# 16_-ETH_SWITCH.net
KiCad netlist of a schematic drawn in Altium Designer
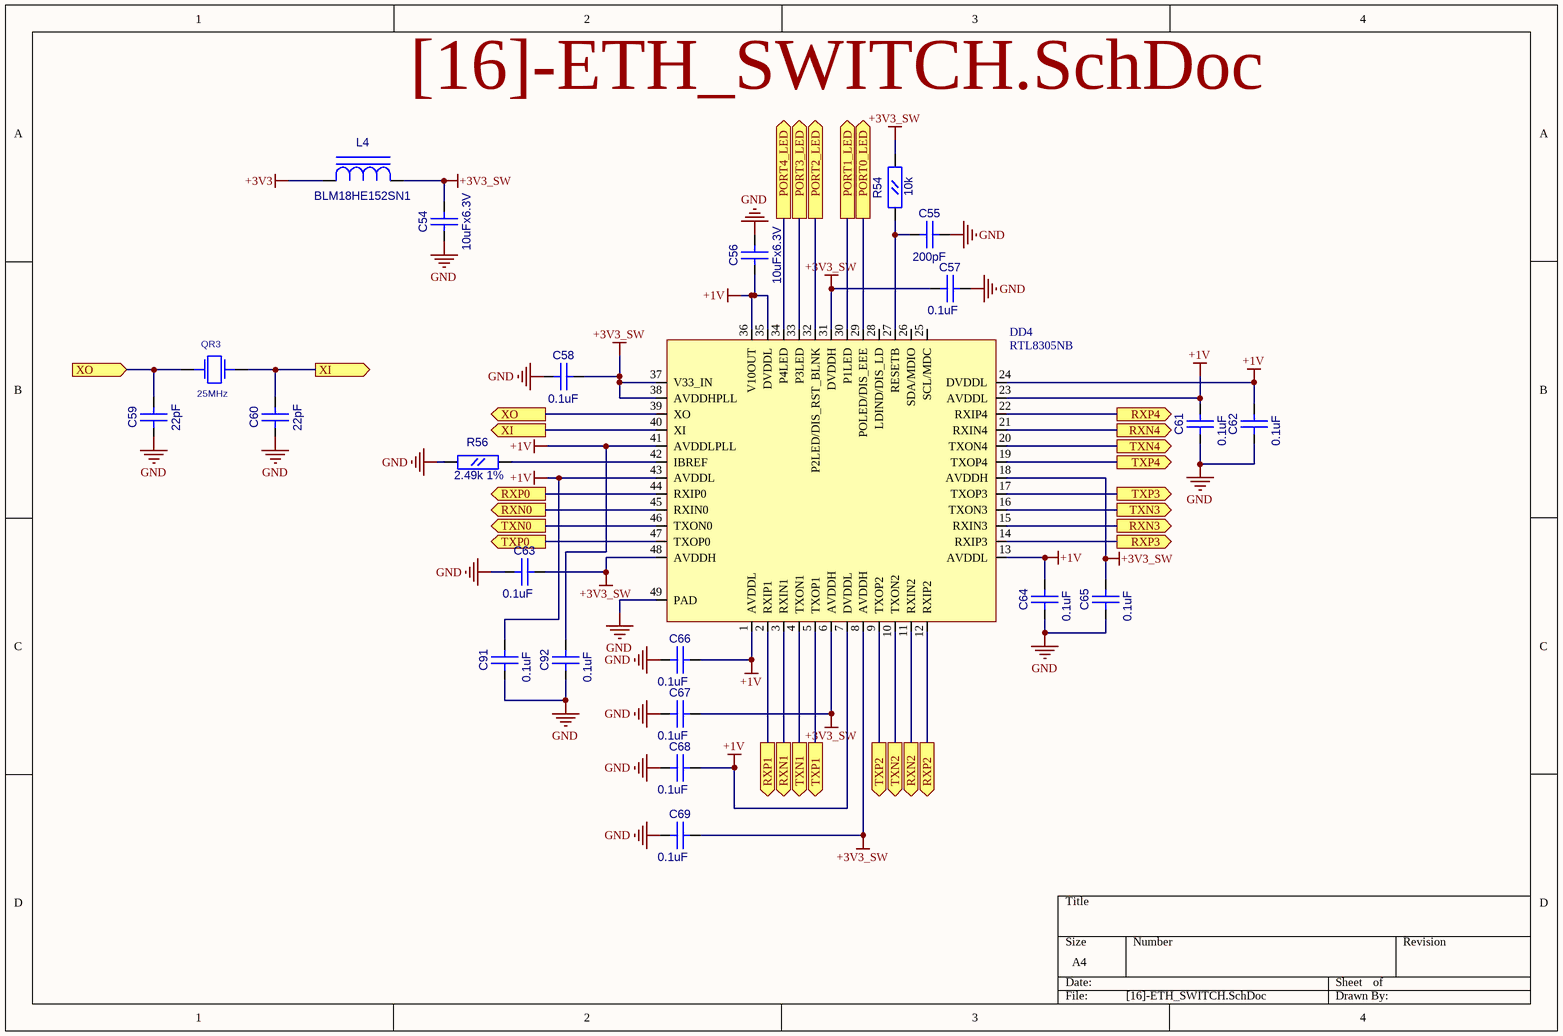
[diagram p0: [16]-ETH_SWITCH.SchDoc]

(export (version "E")
  (design (tool "Eeschema 10.0.6"))
  (components
    (comp (ref "C54")
      (value "10uFx6.3V")
      (footprint "CC0805")
      (description "CC0805")
      (libsource (lib "fizik_lib") (part "CC0805"))
    )
    (comp (ref "C55")
      (value "200pF")
      (footprint "CC0603")
      (description "CC0603")
      (libsource (lib "fizik_lib") (part "CC0603"))
    )
    (comp (ref "C56")
      (value "10uFx6.3V")
      (footprint "CC0805")
      (description "CC0805")
      (libsource (lib "fizik_lib") (part "CC0805"))
    )
    (comp (ref "C57")
      (value "0.1uF")
      (footprint "CC0603")
      (description "CC0603")
      (libsource (lib "fizik_lib") (part "CC0603"))
    )
    (comp (ref "C58")
      (value "0.1uF")
      (footprint "CC0603")
      (description "CC0603")
      (libsource (lib "fizik_lib") (part "CC0603"))
    )
    (comp (ref "C59")
      (value "22pF")
      (footprint "CC0603")
      (description "CC0603")
      (libsource (lib "fizik_lib") (part "CC0603"))
    )
    (comp (ref "C60")
      (value "22pF")
      (footprint "CC0603")
      (description "CC0603")
      (libsource (lib "fizik_lib") (part "CC0603"))
    )
    (comp (ref "C61")
      (value "0.1uF")
      (footprint "CC0603")
      (description "CC0603")
      (libsource (lib "fizik_lib") (part "CC0603"))
    )
    (comp (ref "C62")
      (value "0.1uF")
      (footprint "CC0603")
      (description "CC0603")
      (libsource (lib "fizik_lib") (part "CC0603"))
    )
    (comp (ref "C63")
      (value "0.1uF")
      (footprint "CC0603")
      (description "CC0603")
      (libsource (lib "fizik_lib") (part "CC0603"))
    )
    (comp (ref "C64")
      (value "0.1uF")
      (footprint "CC0603")
      (description "CC0603")
      (libsource (lib "fizik_lib") (part "CC0603"))
    )
    (comp (ref "C65")
      (value "0.1uF")
      (footprint "CC0603")
      (description "CC0603")
      (libsource (lib "fizik_lib") (part "CC0603"))
    )
    (comp (ref "C66")
      (value "0.1uF")
      (footprint "CC0603")
      (description "CC0603")
      (libsource (lib "fizik_lib") (part "CC0603"))
    )
    (comp (ref "C67")
      (value "0.1uF")
      (footprint "CC0603")
      (description "CC0603")
      (libsource (lib "fizik_lib") (part "CC0603"))
    )
    (comp (ref "C68")
      (value "0.1uF")
      (footprint "CC0603")
      (description "CC0603")
      (libsource (lib "fizik_lib") (part "CC0603"))
    )
    (comp (ref "C69")
      (value "0.1uF")
      (footprint "CC0603")
      (description "CC0603")
      (libsource (lib "fizik_lib") (part "CC0603"))
    )
    (comp (ref "C91")
      (value "0.1uF")
      (footprint "CC0603")
      (description "CC0603")
      (libsource (lib "fizik_lib") (part "CC0603"))
    )
    (comp (ref "C92")
      (value "0.1uF")
      (footprint "CC0603")
      (description "CC0603")
      (libsource (lib "fizik_lib") (part "CC0603"))
    )
    (comp (ref "DD4")
      (value "RTL8305NB")
      (footprint "QFN48_ISL")
      (libsource (lib "fizik_lib") (part "RTL8305NB"))
    )
    (comp (ref "L4")
      (value "BLM18HE152SN1")
      (footprint "L0603")
      (description "L0603")
      (libsource (lib "gprs_modem_2") (part "L0603"))
    )
    (comp (ref "QR3")
      (value "25MHz")
      (footprint "AC5032_2")
      (description "AC5032/2")
      (libsource (lib "fizik_lib") (part "AC5032_2"))
    )
    (comp (ref "R54")
      (value "10k")
      (footprint "RC0603")
      (description "RC0603")
      (libsource (lib "fizik_lib") (part "RC0603"))
    )
    (comp (ref "R56")
      (value "2.49k 1%")
      (footprint "RC0603")
      (description "RC0603")
      (libsource (lib "fizik_lib") (part "RC0603"))
    )
  )
  (nets
    (net (code "1") (name "+1V") (class "Default")
      (node (ref "C56") (pin "1") (pinfunction "A_1") (pintype "passive"))
      (node (ref "C61") (pin "2") (pinfunction "B_2") (pintype "passive"))
      (node (ref "C62") (pin "2") (pinfunction "B_2") (pintype "passive"))
      (node (ref "C64") (pin "2") (pinfunction "B_2") (pintype "passive"))
      (node (ref "C66") (pin "2") (pinfunction "B_2") (pintype "passive"))
      (node (ref "C68") (pin "2") (pinfunction "B_2") (pintype "passive"))
      (node (ref "C91") (pin "2") (pinfunction "B_2") (pintype "passive"))
      (node (ref "C92") (pin "2") (pinfunction "B_2") (pintype "passive"))
      (node (ref "DD4") (pin "1") (pinfunction "AVDDL_1") (pintype "passive"))
      (node (ref "DD4") (pin "13") (pinfunction "AVDDL_13") (pintype "passive"))
      (node (ref "DD4") (pin "23") (pinfunction "AVDDL_23") (pintype "passive"))
      (node (ref "DD4") (pin "24") (pinfunction "DVDDL_24") (pintype "passive"))
      (node (ref "DD4") (pin "35") (pinfunction "DVDDL_35") (pintype "passive"))
      (node (ref "DD4") (pin "36") (pinfunction "V10OUT_36") (pintype "passive"))
      (node (ref "DD4") (pin "41") (pinfunction "AVDDLPLL_41") (pintype "passive"))
      (node (ref "DD4") (pin "43") (pinfunction "AVDDL_43") (pintype "passive"))
      (node (ref "DD4") (pin "7") (pinfunction "DVDDL_7") (pintype "passive"))
    )
    (net (code "2") (name "+3V3") (class "Default")
      (node (ref "L4") (pin "1") (pinfunction "A_1") (pintype "passive"))
    )
    (net (code "3") (name "+3V3_SW") (class "Default")
      (node (ref "C54") (pin "2") (pinfunction "B_2") (pintype "passive"))
      (node (ref "C57") (pin "1") (pinfunction "A_1") (pintype "passive"))
      (node (ref "C58") (pin "2") (pinfunction "B_2") (pintype "passive"))
      (node (ref "C63") (pin "2") (pinfunction "B_2") (pintype "passive"))
      (node (ref "C65") (pin "2") (pinfunction "B_2") (pintype "passive"))
      (node (ref "C67") (pin "2") (pinfunction "B_2") (pintype "passive"))
      (node (ref "C69") (pin "2") (pinfunction "B_2") (pintype "passive"))
      (node (ref "DD4") (pin "18") (pinfunction "AVDDH_18") (pintype "passive"))
      (node (ref "DD4") (pin "31") (pinfunction "DVDDH_31") (pintype "passive"))
      (node (ref "DD4") (pin "37") (pinfunction "V33_IN_37") (pintype "passive"))
      (node (ref "DD4") (pin "38") (pinfunction "AVDDHPLL_38") (pintype "passive"))
      (node (ref "DD4") (pin "48") (pinfunction "AVDDH_48") (pintype "passive"))
      (node (ref "DD4") (pin "6") (pinfunction "AVDDH_6") (pintype "passive"))
      (node (ref "DD4") (pin "8") (pinfunction "AVDDH_8") (pintype "passive"))
      (node (ref "L4") (pin "2") (pinfunction "C_2") (pintype "passive"))
      (node (ref "R54") (pin "2") (pinfunction "B_2") (pintype "passive"))
    )
    (net (code "4") (name "/PORT0_LED") (class "Default")
      (node (ref "DD4") (pin "29") (pinfunction "POLED/DIS_EEE_29") (pintype "passive"))
    )
    (net (code "5") (name "/PORT1_LED") (class "Default")
      (node (ref "DD4") (pin "30") (pinfunction "P1LED_30") (pintype "passive"))
    )
    (net (code "6") (name "/PORT2_LED") (class "Default")
      (node (ref "DD4") (pin "32") (pinfunction "P2LED/DIS_RST_BLNK_32") (pintype "passive"))
    )
    (net (code "7") (name "/PORT3_LED") (class "Default")
      (node (ref "DD4") (pin "33") (pinfunction "P3LED_33") (pintype "passive"))
    )
    (net (code "8") (name "/PORT4_LED") (class "Default")
      (node (ref "DD4") (pin "34") (pinfunction "P4LED_34") (pintype "passive"))
    )
    (net (code "9") (name "/RXN0") (class "Default")
      (node (ref "DD4") (pin "45") (pinfunction "RXIN0_45") (pintype "passive"))
    )
    (net (code "10") (name "/RXN1") (class "Default")
      (node (ref "DD4") (pin "3") (pinfunction "RXIN1_3") (pintype "passive"))
    )
    (net (code "11") (name "/RXN2") (class "Default")
      (node (ref "DD4") (pin "11") (pinfunction "RXIN2_11") (pintype "passive"))
    )
    (net (code "12") (name "/RXN3") (class "Default")
      (node (ref "DD4") (pin "15") (pinfunction "RXIN3_15") (pintype "passive"))
    )
    (net (code "13") (name "/RXN4") (class "Default")
      (node (ref "DD4") (pin "21") (pinfunction "RXIN4_21") (pintype "passive"))
    )
    (net (code "14") (name "/RXP0") (class "Default")
      (node (ref "DD4") (pin "44") (pinfunction "RXIP0_44") (pintype "passive"))
    )
    (net (code "15") (name "/RXP1") (class "Default")
      (node (ref "DD4") (pin "2") (pinfunction "RXIP1_2") (pintype "passive"))
    )
    (net (code "16") (name "/RXP2") (class "Default")
      (node (ref "DD4") (pin "12") (pinfunction "RXIP2_12") (pintype "passive"))
    )
    (net (code "17") (name "/RXP3") (class "Default")
      (node (ref "DD4") (pin "14") (pinfunction "RXIP3_14") (pintype "passive"))
    )
    (net (code "18") (name "/RXP4") (class "Default")
      (node (ref "DD4") (pin "22") (pinfunction "RXIP4_22") (pintype "passive"))
    )
    (net (code "19") (name "/TXN0") (class "Default")
      (node (ref "DD4") (pin "46") (pinfunction "TXON0_46") (pintype "passive"))
    )
    (net (code "20") (name "/TXN1") (class "Default")
      (node (ref "DD4") (pin "4") (pinfunction "TXON1_4") (pintype "passive"))
    )
    (net (code "21") (name "/TXN2") (class "Default")
      (node (ref "DD4") (pin "10") (pinfunction "TXON2_10") (pintype "passive"))
    )
    (net (code "22") (name "/TXN3") (class "Default")
      (node (ref "DD4") (pin "16") (pinfunction "TXON3_16") (pintype "passive"))
    )
    (net (code "23") (name "/TXN4") (class "Default")
      (node (ref "DD4") (pin "20") (pinfunction "TXON4_20") (pintype "passive"))
    )
    (net (code "24") (name "/TXP0") (class "Default")
      (node (ref "DD4") (pin "47") (pinfunction "TXOP0_47") (pintype "passive"))
    )
    (net (code "25") (name "/TXP1") (class "Default")
      (node (ref "DD4") (pin "5") (pinfunction "TXOP1_5") (pintype "passive"))
    )
    (net (code "26") (name "/TXP2") (class "Default")
      (node (ref "DD4") (pin "9") (pinfunction "TXOP2_9") (pintype "passive"))
    )
    (net (code "27") (name "/TXP3") (class "Default")
      (node (ref "DD4") (pin "17") (pinfunction "TXOP3_17") (pintype "passive"))
    )
    (net (code "28") (name "/TXP4") (class "Default")
      (node (ref "DD4") (pin "19") (pinfunction "TXOP4_19") (pintype "passive"))
    )
    (net (code "29") (name "/XI") (class "Default")
      (node (ref "C60") (pin "2") (pinfunction "B_2") (pintype "passive"))
      (node (ref "DD4") (pin "40") (pinfunction "XI_40") (pintype "passive"))
      (node (ref "QR3") (pin "2") (pintype "passive"))
    )
    (net (code "30") (name "/XO") (class "Default")
      (node (ref "C59") (pin "2") (pinfunction "B_2") (pintype "passive"))
      (node (ref "DD4") (pin "39") (pinfunction "XO_39") (pintype "passive"))
      (node (ref "QR3") (pin "1") (pintype "passive"))
    )
    (net (code "31") (name "GND") (class "Default")
      (node (ref "C54") (pin "1") (pinfunction "A_1") (pintype "passive"))
      (node (ref "C55") (pin "2") (pinfunction "B_2") (pintype "passive"))
      (node (ref "C56") (pin "2") (pinfunction "B_2") (pintype "passive"))
      (node (ref "C57") (pin "2") (pinfunction "B_2") (pintype "passive"))
      (node (ref "C58") (pin "1") (pinfunction "A_1") (pintype "passive"))
      (node (ref "C59") (pin "1") (pinfunction "A_1") (pintype "passive"))
      (node (ref "C60") (pin "1") (pinfunction "A_1") (pintype "passive"))
      (node (ref "C61") (pin "1") (pinfunction "A_1") (pintype "passive"))
      (node (ref "C62") (pin "1") (pinfunction "A_1") (pintype "passive"))
      (node (ref "C63") (pin "1") (pinfunction "A_1") (pintype "passive"))
      (node (ref "C64") (pin "1") (pinfunction "A_1") (pintype "passive"))
      (node (ref "C65") (pin "1") (pinfunction "A_1") (pintype "passive"))
      (node (ref "C66") (pin "1") (pinfunction "A_1") (pintype "passive"))
      (node (ref "C67") (pin "1") (pinfunction "A_1") (pintype "passive"))
      (node (ref "C68") (pin "1") (pinfunction "A_1") (pintype "passive"))
      (node (ref "C69") (pin "1") (pinfunction "A_1") (pintype "passive"))
      (node (ref "C91") (pin "1") (pinfunction "A_1") (pintype "passive"))
      (node (ref "C92") (pin "1") (pinfunction "A_1") (pintype "passive"))
      (node (ref "DD4") (pin "49") (pinfunction "PAD_49") (pintype "passive"))
      (node (ref "R56") (pin "1") (pinfunction "A_1") (pintype "passive"))
    )
    (net (code "32") (name "Net-(C55-A)") (class "Default")
      (node (ref "C55") (pin "1") (pinfunction "A_1") (pintype "passive"))
      (node (ref "DD4") (pin "27") (pinfunction "RESETB_27") (pintype "passive"))
      (node (ref "R54") (pin "1") (pinfunction "A_1") (pintype "passive"))
    )
    (net (code "33") (name "Net-(DD4-IBREF)") (class "Default")
      (node (ref "DD4") (pin "42") (pinfunction "IBREF_42") (pintype "passive"))
      (node (ref "R56") (pin "2") (pinfunction "B_2") (pintype "passive"))
    )
    (net (code "34") (name "unconnected-(DD4-LDIND{slash}DIS_LD-Pad28)") (class "Default")
      (node (ref "DD4") (pin "28") (pinfunction "LDIND/DIS_LD_28") (pintype "passive"))
    )
    (net (code "35") (name "unconnected-(DD4-SCL{slash}MDC-Pad25)") (class "Default")
      (node (ref "DD4") (pin "25") (pinfunction "SCL/MDC_25") (pintype "passive"))
    )
    (net (code "36") (name "unconnected-(DD4-SDA{slash}MDIO-Pad26)") (class "Default")
      (node (ref "DD4") (pin "26") (pinfunction "SDA/MDIO_26") (pintype "passive"))
    )
  )
)
